# LVDS.net
KiCad netlist of a schematic drawn in Altium Designer
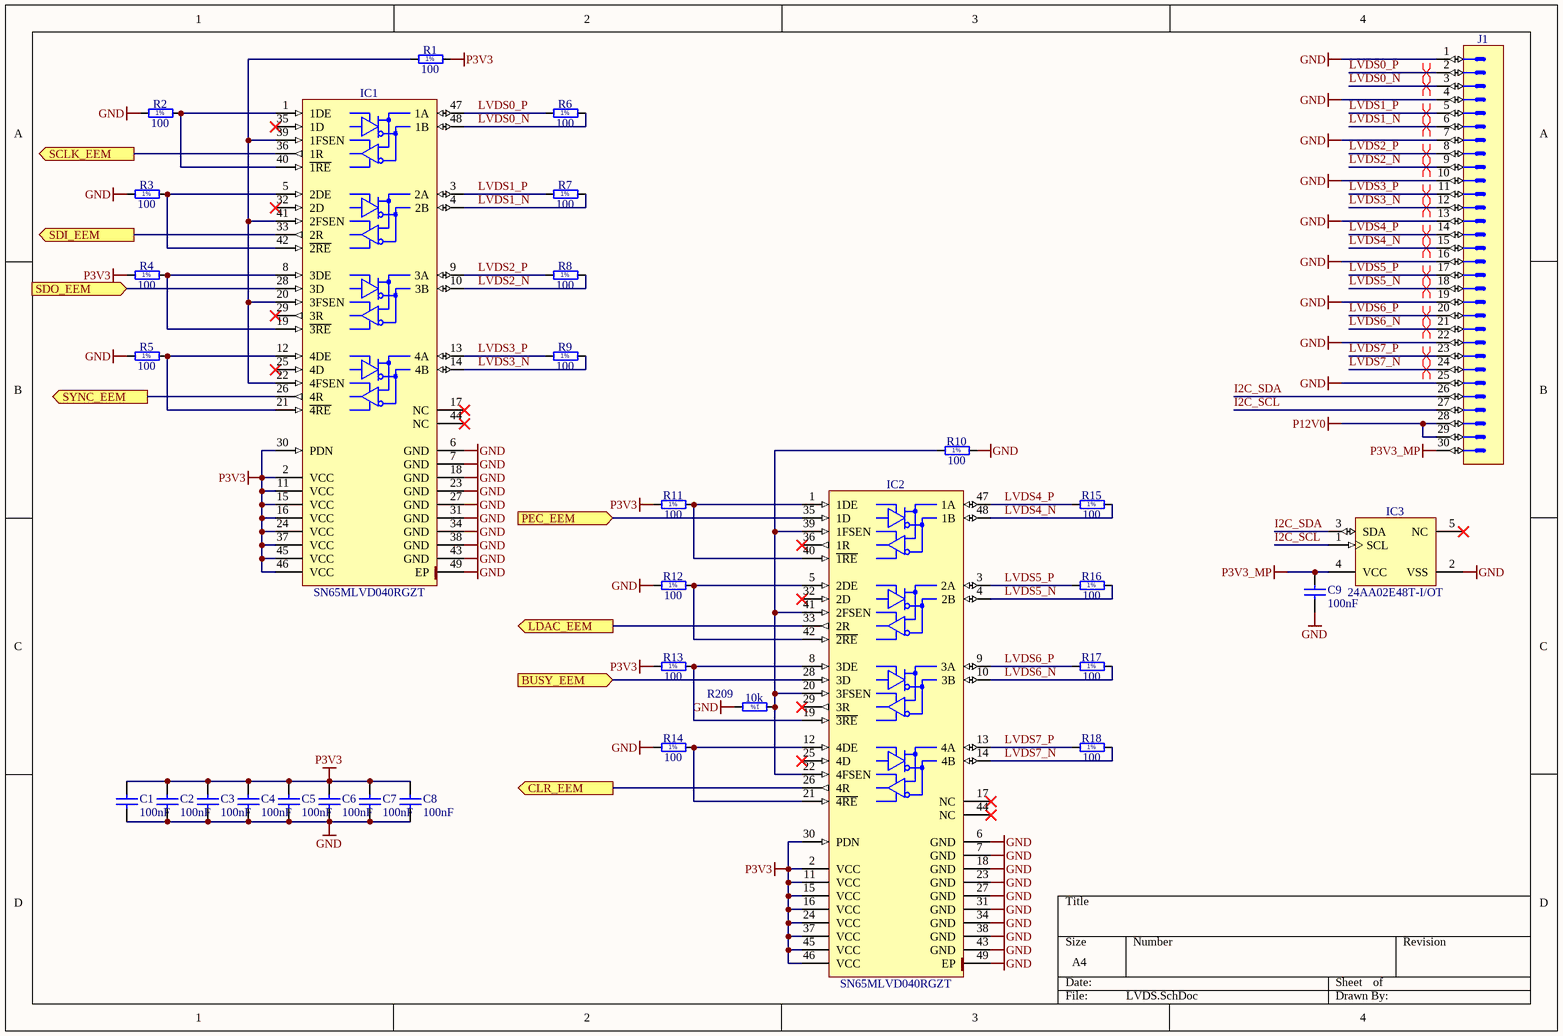
[diagram p0: LVDS.SchDoc]

(export (version "E")
  (design (tool "Eeschema 10.0.6"))
  (components
    (comp (ref "C1")
      (value "100nF")
      (footprint "C0402C104K4RACTU")
      (description "Capacitor; Ceramic; Cap; .100uF; Tol 10%; SMT; Vol-Rtg 16V; X7R; Tape and Reel")
      (fields (field (name "TOLERANCE") "10%"))
      (libsource (lib "CapacitorLibrary") (part "C0402C104K4RACTU"))
    )
    (comp (ref "C2")
      (value "100nF")
      (footprint "C0402C104K4RACTU")
      (description "Capacitor; Ceramic; Cap; .100uF; Tol 10%; SMT; Vol-Rtg 16V; X7R; Tape and Reel")
      (fields (field (name "TOLERANCE") "10%"))
      (libsource (lib "CapacitorLibrary") (part "C0402C104K4RACTU"))
    )
    (comp (ref "C3")
      (value "100nF")
      (footprint "C0402C104K4RACTU")
      (description "Capacitor; Ceramic; Cap; .100uF; Tol 10%; SMT; Vol-Rtg 16V; X7R; Tape and Reel")
      (fields (field (name "TOLERANCE") "10%"))
      (libsource (lib "CapacitorLibrary") (part "C0402C104K4RACTU"))
    )
    (comp (ref "C4")
      (value "100nF")
      (footprint "C0402C104K4RACTU")
      (description "Capacitor; Ceramic; Cap; .100uF; Tol 10%; SMT; Vol-Rtg 16V; X7R; Tape and Reel")
      (fields (field (name "TOLERANCE") "10%"))
      (libsource (lib "CapacitorLibrary") (part "C0402C104K4RACTU"))
    )
    (comp (ref "C5")
      (value "100nF")
      (footprint "C0402C104K4RACTU")
      (description "Capacitor; Ceramic; Cap; .100uF; Tol 10%; SMT; Vol-Rtg 16V; X7R; Tape and Reel")
      (fields (field (name "TOLERANCE") "10%"))
      (libsource (lib "CapacitorLibrary") (part "C0402C104K4RACTU"))
    )
    (comp (ref "C6")
      (value "100nF")
      (footprint "C0402C104K4RACTU")
      (description "Capacitor; Ceramic; Cap; .100uF; Tol 10%; SMT; Vol-Rtg 16V; X7R; Tape and Reel")
      (fields (field (name "TOLERANCE") "10%"))
      (libsource (lib "CapacitorLibrary") (part "C0402C104K4RACTU"))
    )
    (comp (ref "C7")
      (value "100nF")
      (footprint "C0402C104K4RACTU")
      (description "Capacitor; Ceramic; Cap; .100uF; Tol 10%; SMT; Vol-Rtg 16V; X7R; Tape and Reel")
      (fields (field (name "TOLERANCE") "10%"))
      (libsource (lib "CapacitorLibrary") (part "C0402C104K4RACTU"))
    )
    (comp (ref "C8")
      (value "100nF")
      (footprint "C0402C104K4RACTU")
      (description "Capacitor; Ceramic; Cap; .100uF; Tol 10%; SMT; Vol-Rtg 16V; X7R; Tape and Reel")
      (fields (field (name "TOLERANCE") "10%"))
      (libsource (lib "CapacitorLibrary") (part "C0402C104K4RACTU"))
    )
    (comp (ref "C9")
      (value "100nF")
      (footprint "C0402C104K4RACTU")
      (description "Capacitor; Ceramic; Cap; .100uF; Tol 10%; SMT; Vol-Rtg 16V; X7R; Tape and Reel")
      (fields (field (name "TOLERANCE") "10%"))
      (libsource (lib "CapacitorLibrary") (part "C0402C104K4RACTU"))
    )
    (comp (ref "IC1")
      (value "SN65MLVD040RGZT")
      (footprint "QFN50P700X700X100-49N-S420")
      (description "4-Channel Half-Duplex M-LVDS Line Transceiver")
      (fields (field (name "MANUFACTURER") "TEXAS INSTRUMENTS") (field (name "AUTHOR") "CERN DEM JLC"))
      (libsource (lib "ICs And Semiconductors") (part "SN65MLVD040"))
    )
    (comp (ref "IC2")
      (value "SN65MLVD040RGZT")
      (footprint "QFN50P700X700X100-49N-S420")
      (description "4-Channel Half-Duplex M-LVDS Line Transceiver")
      (fields (field (name "MANUFACTURER") "TEXAS INSTRUMENTS") (field (name "AUTHOR") "CERN DEM JLC"))
      (libsource (lib "ICs And Semiconductors") (part "SN65MLVD040"))
    )
    (comp (ref "IC3")
      (value "24AA02E48T-I/OT")
      (footprint "SOT95P280X145-5N")
      (description "1.7V-5.5V, 2K I2C Serial EEPROM With EUI-48 Node Identity")
      (fields (field (name "MANUFACTURER") "MICROCHIP TECHNOLOGY") (field (name "AUTHOR") "CERN DEM MR"))
      (libsource (lib "ICs And Semiconductors") (part "24AA02E48T-I/OT"))
    )
    (comp (ref "J1")
      (value "Header 30")
      (footprint "3M_N2530-6002RB")
      (description "Connector 30 Male")
      (fields
        (field (name "PART NUMBER") "3M_N2530-6002RB")
        (field (name "MANUFACTURER") "3M")
        (field (name "AUTHOR") "CERN DEM JLC")
      )
      (libsource (lib "Connectors") (part "Connector 30 Male"))
    )
    (comp (ref "R1")
      (value "100")
      (footprint "RESC1005X40N")
      (description "Resistor - 1%")
      (fields
        (field (name "PART NUMBER") "R0402_100R_1%_0.1W_100PPM")
        (field (name "POWER") "0.1W")
        (field (name "AUTHOR") "CERN DEM JLC")
      )
      (libsource (lib "Resistors") (part "Resistor - 1%"))
    )
    (comp (ref "R2")
      (value "100")
      (footprint "RESC1005X40N")
      (description "Resistor - 1%")
      (fields
        (field (name "PART NUMBER") "R0402_100R_1%_0.1W_100PPM")
        (field (name "POWER") "0.1W")
        (field (name "AUTHOR") "CERN DEM JLC")
      )
      (libsource (lib "Resistors") (part "Resistor - 1%"))
    )
    (comp (ref "R3")
      (value "100")
      (footprint "RESC1005X40N")
      (description "Resistor - 1%")
      (fields
        (field (name "PART NUMBER") "R0402_100R_1%_0.1W_100PPM")
        (field (name "POWER") "0.1W")
        (field (name "AUTHOR") "CERN DEM JLC")
      )
      (libsource (lib "Resistors") (part "Resistor - 1%"))
    )
    (comp (ref "R4")
      (value "100")
      (footprint "RESC1005X40N")
      (description "Resistor - 1%")
      (fields
        (field (name "PART NUMBER") "R0402_100R_1%_0.1W_100PPM")
        (field (name "POWER") "0.1W")
        (field (name "AUTHOR") "CERN DEM JLC")
      )
      (libsource (lib "Resistors") (part "Resistor - 1%"))
    )
    (comp (ref "R5")
      (value "100")
      (footprint "RESC1005X40N")
      (description "Resistor - 1%")
      (fields
        (field (name "PART NUMBER") "R0402_100R_1%_0.1W_100PPM")
        (field (name "POWER") "0.1W")
        (field (name "AUTHOR") "CERN DEM JLC")
      )
      (libsource (lib "Resistors") (part "Resistor - 1%"))
    )
    (comp (ref "R6")
      (value "100")
      (footprint "RESC1005X40N")
      (description "Resistor - 1%")
      (fields
        (field (name "PART NUMBER") "R0402_100R_1%_0.1W_100PPM")
        (field (name "POWER") "0.1W")
        (field (name "AUTHOR") "CERN DEM JLC")
      )
      (libsource (lib "Resistors") (part "Resistor - 1%"))
    )
    (comp (ref "R7")
      (value "100")
      (footprint "RESC1005X40N")
      (description "Resistor - 1%")
      (fields
        (field (name "PART NUMBER") "R0402_100R_1%_0.1W_100PPM")
        (field (name "POWER") "0.1W")
        (field (name "AUTHOR") "CERN DEM JLC")
      )
      (libsource (lib "Resistors") (part "Resistor - 1%"))
    )
    (comp (ref "R8")
      (value "100")
      (footprint "RESC1005X40N")
      (description "Resistor - 1%")
      (fields
        (field (name "PART NUMBER") "R0402_100R_1%_0.1W_100PPM")
        (field (name "POWER") "0.1W")
        (field (name "AUTHOR") "CERN DEM JLC")
      )
      (libsource (lib "Resistors") (part "Resistor - 1%"))
    )
    (comp (ref "R9")
      (value "100")
      (footprint "RESC1005X40N")
      (description "Resistor - 1%")
      (fields
        (field (name "PART NUMBER") "R0402_100R_1%_0.1W_100PPM")
        (field (name "POWER") "0.1W")
        (field (name "AUTHOR") "CERN DEM JLC")
      )
      (libsource (lib "Resistors") (part "Resistor - 1%"))
    )
    (comp (ref "R10")
      (value "100")
      (footprint "RESC1005X40N")
      (description "Resistor - 1%")
      (fields
        (field (name "PART NUMBER") "R0402_100R_1%_0.1W_100PPM")
        (field (name "POWER") "0.1W")
        (field (name "AUTHOR") "CERN DEM JLC")
      )
      (libsource (lib "Resistors") (part "Resistor - 1%"))
    )
    (comp (ref "R11")
      (value "100")
      (footprint "RESC1005X40N")
      (description "Resistor - 1%")
      (fields
        (field (name "PART NUMBER") "R0402_100R_1%_0.1W_100PPM")
        (field (name "POWER") "0.1W")
        (field (name "AUTHOR") "CERN DEM JLC")
      )
      (libsource (lib "Resistors") (part "Resistor - 1%"))
    )
    (comp (ref "R12")
      (value "100")
      (footprint "RESC1005X40N")
      (description "Resistor - 1%")
      (fields
        (field (name "PART NUMBER") "R0402_100R_1%_0.1W_100PPM")
        (field (name "POWER") "0.1W")
        (field (name "AUTHOR") "CERN DEM JLC")
      )
      (libsource (lib "Resistors") (part "Resistor - 1%"))
    )
    (comp (ref "R13")
      (value "100")
      (footprint "RESC1005X40N")
      (description "Resistor - 1%")
      (fields
        (field (name "PART NUMBER") "R0402_100R_1%_0.1W_100PPM")
        (field (name "POWER") "0.1W")
        (field (name "AUTHOR") "CERN DEM JLC")
      )
      (libsource (lib "Resistors") (part "Resistor - 1%"))
    )
    (comp (ref "R14")
      (value "100")
      (footprint "RESC1005X40N")
      (description "Resistor - 1%")
      (fields
        (field (name "PART NUMBER") "R0402_100R_1%_0.1W_100PPM")
        (field (name "POWER") "0.1W")
        (field (name "AUTHOR") "CERN DEM JLC")
      )
      (libsource (lib "Resistors") (part "Resistor - 1%"))
    )
    (comp (ref "R15")
      (value "100")
      (footprint "RESC1005X40N")
      (description "Resistor - 1%")
      (fields
        (field (name "PART NUMBER") "R0402_100R_1%_0.1W_100PPM")
        (field (name "POWER") "0.1W")
        (field (name "AUTHOR") "CERN DEM JLC")
      )
      (libsource (lib "Resistors") (part "Resistor - 1%"))
    )
    (comp (ref "R16")
      (value "100")
      (footprint "RESC1005X40N")
      (description "Resistor - 1%")
      (fields
        (field (name "PART NUMBER") "R0402_100R_1%_0.1W_100PPM")
        (field (name "POWER") "0.1W")
        (field (name "AUTHOR") "CERN DEM JLC")
      )
      (libsource (lib "Resistors") (part "Resistor - 1%"))
    )
    (comp (ref "R17")
      (value "100")
      (footprint "RESC1005X40N")
      (description "Resistor - 1%")
      (fields
        (field (name "PART NUMBER") "R0402_100R_1%_0.1W_100PPM")
        (field (name "POWER") "0.1W")
        (field (name "AUTHOR") "CERN DEM JLC")
      )
      (libsource (lib "Resistors") (part "Resistor - 1%"))
    )
    (comp (ref "R18")
      (value "100")
      (footprint "RESC1005X40N")
      (description "Resistor - 1%")
      (fields
        (field (name "PART NUMBER") "R0402_100R_1%_0.1W_100PPM")
        (field (name "POWER") "0.1W")
        (field (name "AUTHOR") "CERN DEM JLC")
      )
      (libsource (lib "Resistors") (part "Resistor - 1%"))
    )
    (comp (ref "R209")
      (value "10k")
      (footprint "RESC1005X40N")
      (description "Resistor - 1%")
      (fields
        (field (name "PART NUMBER") "R0402_10K_1%_0.0625W_100PPM")
        (field (name "POWER") "0.0625W")
        (field (name "AUTHOR") "CERN DEM JLC")
      )
      (libsource (lib "Resistors") (part "Resistor - 1%"))
    )
  )
  (nets
    (net (code "1") (name "/BUSY_EEM") (class "Default")
      (node (ref "IC2") (pin "28") (pinfunction "3D_28") (pintype "input"))
    )
    (net (code "2") (name "/CLR_EEM") (class "Default")
      (node (ref "IC2") (pin "26") (pinfunction "4R_26") (pintype "output"))
    )
    (net (code "3") (name "/I2C_SCL") (class "Default")
      (node (ref "IC3") (pin "1") (pinfunction "SCL_1") (pintype "input"))
      (node (ref "J1") (pin "27") (pinfunction "27_27") (pintype "bidirectional"))
    )
    (net (code "4") (name "/I2C_SDA") (class "Default")
      (node (ref "IC3") (pin "3") (pinfunction "SDA_3") (pintype "bidirectional"))
      (node (ref "J1") (pin "26") (pinfunction "26_26") (pintype "bidirectional"))
    )
    (net (code "5") (name "/LDAC_EEM") (class "Default")
      (node (ref "IC2") (pin "33") (pinfunction "2R_33") (pintype "output"))
    )
    (net (code "6") (name "/LVDS0_N") (class "Default")
      (node (ref "IC1") (pin "48") (pinfunction "1B_48") (pintype "bidirectional"))
      (node (ref "J1") (pin "3") (pinfunction "3_3") (pintype "bidirectional"))
      (node (ref "R6") (pin "2") (pinfunction "2_2") (pintype "passive"))
    )
    (net (code "7") (name "/LVDS0_P") (class "Default")
      (node (ref "IC1") (pin "47") (pinfunction "1A_47") (pintype "bidirectional"))
      (node (ref "J1") (pin "2") (pinfunction "2_2") (pintype "bidirectional"))
      (node (ref "R6") (pin "1") (pinfunction "1_1") (pintype "passive"))
    )
    (net (code "8") (name "/LVDS1_N") (class "Default")
      (node (ref "IC1") (pin "4") (pinfunction "2B_4") (pintype "bidirectional"))
      (node (ref "J1") (pin "6") (pinfunction "6_6") (pintype "bidirectional"))
      (node (ref "R7") (pin "2") (pinfunction "2_2") (pintype "passive"))
    )
    (net (code "9") (name "/LVDS1_P") (class "Default")
      (node (ref "IC1") (pin "3") (pinfunction "2A_3") (pintype "bidirectional"))
      (node (ref "J1") (pin "5") (pinfunction "5_5") (pintype "bidirectional"))
      (node (ref "R7") (pin "1") (pinfunction "1_1") (pintype "passive"))
    )
    (net (code "10") (name "/LVDS2_N") (class "Default")
      (node (ref "IC1") (pin "10") (pinfunction "3B_10") (pintype "bidirectional"))
      (node (ref "J1") (pin "9") (pinfunction "9_9") (pintype "bidirectional"))
      (node (ref "R8") (pin "2") (pinfunction "2_2") (pintype "passive"))
    )
    (net (code "11") (name "/LVDS2_P") (class "Default")
      (node (ref "IC1") (pin "9") (pinfunction "3A_9") (pintype "bidirectional"))
      (node (ref "J1") (pin "8") (pinfunction "8_8") (pintype "bidirectional"))
      (node (ref "R8") (pin "1") (pinfunction "1_1") (pintype "passive"))
    )
    (net (code "12") (name "/LVDS3_N") (class "Default")
      (node (ref "IC1") (pin "14") (pinfunction "4B_14") (pintype "bidirectional"))
      (node (ref "J1") (pin "12") (pinfunction "12_12") (pintype "bidirectional"))
      (node (ref "R9") (pin "2") (pinfunction "2_2") (pintype "passive"))
    )
    (net (code "13") (name "/LVDS3_P") (class "Default")
      (node (ref "IC1") (pin "13") (pinfunction "4A_13") (pintype "bidirectional"))
      (node (ref "J1") (pin "11") (pinfunction "11_11") (pintype "bidirectional"))
      (node (ref "R9") (pin "1") (pinfunction "1_1") (pintype "passive"))
    )
    (net (code "14") (name "/LVDS4_N") (class "Default")
      (node (ref "IC2") (pin "48") (pinfunction "1B_48") (pintype "bidirectional"))
      (node (ref "J1") (pin "15") (pinfunction "15_15") (pintype "bidirectional"))
      (node (ref "R15") (pin "2") (pinfunction "2_2") (pintype "passive"))
    )
    (net (code "15") (name "/LVDS4_P") (class "Default")
      (node (ref "IC2") (pin "47") (pinfunction "1A_47") (pintype "bidirectional"))
      (node (ref "J1") (pin "14") (pinfunction "14_14") (pintype "bidirectional"))
      (node (ref "R15") (pin "1") (pinfunction "1_1") (pintype "passive"))
    )
    (net (code "16") (name "/LVDS5_N") (class "Default")
      (node (ref "IC2") (pin "4") (pinfunction "2B_4") (pintype "bidirectional"))
      (node (ref "J1") (pin "18") (pinfunction "18_18") (pintype "bidirectional"))
      (node (ref "R16") (pin "2") (pinfunction "2_2") (pintype "passive"))
    )
    (net (code "17") (name "/LVDS5_P") (class "Default")
      (node (ref "IC2") (pin "3") (pinfunction "2A_3") (pintype "bidirectional"))
      (node (ref "J1") (pin "17") (pinfunction "17_17") (pintype "bidirectional"))
      (node (ref "R16") (pin "1") (pinfunction "1_1") (pintype "passive"))
    )
    (net (code "18") (name "/LVDS6_N") (class "Default")
      (node (ref "IC2") (pin "10") (pinfunction "3B_10") (pintype "bidirectional"))
      (node (ref "J1") (pin "21") (pinfunction "21_21") (pintype "bidirectional"))
      (node (ref "R17") (pin "2") (pinfunction "2_2") (pintype "passive"))
    )
    (net (code "19") (name "/LVDS6_P") (class "Default")
      (node (ref "IC2") (pin "9") (pinfunction "3A_9") (pintype "bidirectional"))
      (node (ref "J1") (pin "20") (pinfunction "20_20") (pintype "bidirectional"))
      (node (ref "R17") (pin "1") (pinfunction "1_1") (pintype "passive"))
    )
    (net (code "20") (name "/LVDS7_N") (class "Default")
      (node (ref "IC2") (pin "14") (pinfunction "4B_14") (pintype "bidirectional"))
      (node (ref "J1") (pin "24") (pinfunction "24_24") (pintype "bidirectional"))
      (node (ref "R18") (pin "2") (pinfunction "2_2") (pintype "passive"))
    )
    (net (code "21") (name "/LVDS7_P") (class "Default")
      (node (ref "IC2") (pin "13") (pinfunction "4A_13") (pintype "bidirectional"))
      (node (ref "J1") (pin "23") (pinfunction "23_23") (pintype "bidirectional"))
      (node (ref "R18") (pin "1") (pinfunction "1_1") (pintype "passive"))
    )
    (net (code "22") (name "/PEC_EEM") (class "Default")
      (node (ref "IC2") (pin "35") (pinfunction "1D_35") (pintype "input"))
    )
    (net (code "23") (name "/SCLK_EEM") (class "Default")
      (node (ref "IC1") (pin "36") (pinfunction "1R_36") (pintype "output"))
    )
    (net (code "24") (name "/SDI_EEM") (class "Default")
      (node (ref "IC1") (pin "33") (pinfunction "2R_33") (pintype "output"))
    )
    (net (code "25") (name "/SDO_EEM") (class "Default")
      (node (ref "IC1") (pin "28") (pinfunction "3D_28") (pintype "input"))
    )
    (net (code "26") (name "/SYNC_EEM") (class "Default")
      (node (ref "IC1") (pin "26") (pinfunction "4R_26") (pintype "output"))
    )
    (net (code "27") (name "GND") (class "Default")
      (node (ref "C1") (pin "1") (pinfunction "1_1") (pintype "passive"))
      (node (ref "C2") (pin "1") (pinfunction "1_1") (pintype "passive"))
      (node (ref "C3") (pin "1") (pinfunction "1_1") (pintype "passive"))
      (node (ref "C4") (pin "1") (pinfunction "1_1") (pintype "passive"))
      (node (ref "C5") (pin "1") (pinfunction "1_1") (pintype "passive"))
      (node (ref "C6") (pin "1") (pinfunction "1_1") (pintype "passive"))
      (node (ref "C7") (pin "1") (pinfunction "1_1") (pintype "passive"))
      (node (ref "C8") (pin "1") (pinfunction "1_1") (pintype "passive"))
      (node (ref "C9") (pin "1") (pinfunction "1_1") (pintype "passive"))
      (node (ref "IC1") (pin "18") (pinfunction "GND_18") (pintype "power_in"))
      (node (ref "IC1") (pin "23") (pinfunction "GND_23") (pintype "power_in"))
      (node (ref "IC1") (pin "27") (pinfunction "GND_27") (pintype "power_in"))
      (node (ref "IC1") (pin "31") (pinfunction "GND_31") (pintype "power_in"))
      (node (ref "IC1") (pin "34") (pinfunction "GND_34") (pintype "power_in"))
      (node (ref "IC1") (pin "38") (pinfunction "GND_38") (pintype "power_in"))
      (node (ref "IC1") (pin "43") (pinfunction "GND_43") (pintype "power_in"))
      (node (ref "IC1") (pin "49") (pinfunction "EP_49") (pintype "power_in"))
      (node (ref "IC1") (pin "6") (pinfunction "GND_6") (pintype "power_in"))
      (node (ref "IC1") (pin "7") (pinfunction "GND_7") (pintype "power_in"))
      (node (ref "IC2") (pin "18") (pinfunction "GND_18") (pintype "power_in"))
      (node (ref "IC2") (pin "23") (pinfunction "GND_23") (pintype "power_in"))
      (node (ref "IC2") (pin "27") (pinfunction "GND_27") (pintype "power_in"))
      (node (ref "IC2") (pin "31") (pinfunction "GND_31") (pintype "power_in"))
      (node (ref "IC2") (pin "34") (pinfunction "GND_34") (pintype "power_in"))
      (node (ref "IC2") (pin "38") (pinfunction "GND_38") (pintype "power_in"))
      (node (ref "IC2") (pin "43") (pinfunction "GND_43") (pintype "power_in"))
      (node (ref "IC2") (pin "49") (pinfunction "EP_49") (pintype "power_in"))
      (node (ref "IC2") (pin "6") (pinfunction "GND_6") (pintype "power_in"))
      (node (ref "IC2") (pin "7") (pinfunction "GND_7") (pintype "power_in"))
      (node (ref "IC3") (pin "2") (pinfunction "VSS_2") (pintype "power_in"))
      (node (ref "J1") (pin "1") (pinfunction "1_1") (pintype "bidirectional"))
      (node (ref "J1") (pin "10") (pinfunction "10_10") (pintype "bidirectional"))
      (node (ref "J1") (pin "13") (pinfunction "13_13") (pintype "bidirectional"))
      (node (ref "J1") (pin "16") (pinfunction "16_16") (pintype "bidirectional"))
      (node (ref "J1") (pin "19") (pinfunction "19_19") (pintype "bidirectional"))
      (node (ref "J1") (pin "22") (pinfunction "22_22") (pintype "bidirectional"))
      (node (ref "J1") (pin "25") (pinfunction "25_25") (pintype "bidirectional"))
      (node (ref "J1") (pin "4") (pinfunction "4_4") (pintype "bidirectional"))
      (node (ref "J1") (pin "7") (pinfunction "7_7") (pintype "bidirectional"))
      (node (ref "R10") (pin "2") (pinfunction "2_2") (pintype "passive"))
      (node (ref "R12") (pin "1") (pinfunction "1_1") (pintype "passive"))
      (node (ref "R14") (pin "1") (pinfunction "1_1") (pintype "passive"))
      (node (ref "R2") (pin "1") (pinfunction "1_1") (pintype "passive"))
      (node (ref "R209") (pin "2") (pinfunction "2_2") (pintype "passive"))
      (node (ref "R3") (pin "1") (pinfunction "1_1") (pintype "passive"))
      (node (ref "R5") (pin "1") (pinfunction "1_1") (pintype "passive"))
    )
    (net (code "28") (name "Net-(IC1-1DE)") (class "Default")
      (node (ref "IC1") (pin "1") (pinfunction "1DE_1") (pintype "input"))
      (node (ref "IC1") (pin "40") (pinfunction "~{1RE}_40") (pintype "input"))
      (node (ref "R2") (pin "2") (pinfunction "2_2") (pintype "passive"))
    )
    (net (code "29") (name "Net-(IC1-1FSEN)") (class "Default")
      (node (ref "IC1") (pin "20") (pinfunction "3FSEN_20") (pintype "input"))
      (node (ref "IC1") (pin "22") (pinfunction "4FSEN_22") (pintype "input"))
      (node (ref "IC1") (pin "39") (pinfunction "1FSEN_39") (pintype "input"))
      (node (ref "IC1") (pin "41") (pinfunction "2FSEN_41") (pintype "input"))
      (node (ref "R1") (pin "1") (pinfunction "1_1") (pintype "passive"))
    )
    (net (code "30") (name "Net-(IC1-2DE)") (class "Default")
      (node (ref "IC1") (pin "42") (pinfunction "~{2RE}_42") (pintype "input"))
      (node (ref "IC1") (pin "5") (pinfunction "2DE_5") (pintype "input"))
      (node (ref "R3") (pin "2") (pinfunction "2_2") (pintype "passive"))
    )
    (net (code "31") (name "Net-(IC1-3DE)") (class "Default")
      (node (ref "IC1") (pin "19") (pinfunction "~{3RE}_19") (pintype "input"))
      (node (ref "IC1") (pin "8") (pinfunction "3DE_8") (pintype "input"))
      (node (ref "R4") (pin "2") (pinfunction "2_2") (pintype "passive"))
    )
    (net (code "32") (name "Net-(IC1-4DE)") (class "Default")
      (node (ref "IC1") (pin "12") (pinfunction "4DE_12") (pintype "input"))
      (node (ref "IC1") (pin "21") (pinfunction "~{4RE}_21") (pintype "input"))
      (node (ref "R5") (pin "2") (pinfunction "2_2") (pintype "passive"))
    )
    (net (code "33") (name "Net-(IC2-1DE)") (class "Default")
      (node (ref "IC2") (pin "1") (pinfunction "1DE_1") (pintype "input"))
      (node (ref "IC2") (pin "40") (pinfunction "~{1RE}_40") (pintype "input"))
      (node (ref "R11") (pin "2") (pinfunction "2_2") (pintype "passive"))
    )
    (net (code "34") (name "Net-(IC2-1FSEN)") (class "Default")
      (node (ref "IC2") (pin "20") (pinfunction "3FSEN_20") (pintype "input"))
      (node (ref "IC2") (pin "22") (pinfunction "4FSEN_22") (pintype "input"))
      (node (ref "IC2") (pin "39") (pinfunction "1FSEN_39") (pintype "input"))
      (node (ref "IC2") (pin "41") (pinfunction "2FSEN_41") (pintype "input"))
      (node (ref "R10") (pin "1") (pinfunction "1_1") (pintype "passive"))
      (node (ref "R209") (pin "1") (pinfunction "1_1") (pintype "passive"))
    )
    (net (code "35") (name "Net-(IC2-2DE)") (class "Default")
      (node (ref "IC2") (pin "42") (pinfunction "~{2RE}_42") (pintype "input"))
      (node (ref "IC2") (pin "5") (pinfunction "2DE_5") (pintype "input"))
      (node (ref "R12") (pin "2") (pinfunction "2_2") (pintype "passive"))
    )
    (net (code "36") (name "Net-(IC2-3DE)") (class "Default")
      (node (ref "IC2") (pin "19") (pinfunction "~{3RE}_19") (pintype "input"))
      (node (ref "IC2") (pin "8") (pinfunction "3DE_8") (pintype "input"))
      (node (ref "R13") (pin "2") (pinfunction "2_2") (pintype "passive"))
    )
    (net (code "37") (name "Net-(IC2-4DE)") (class "Default")
      (node (ref "IC2") (pin "12") (pinfunction "4DE_12") (pintype "input"))
      (node (ref "IC2") (pin "21") (pinfunction "~{4RE}_21") (pintype "input"))
      (node (ref "R14") (pin "2") (pinfunction "2_2") (pintype "passive"))
    )
    (net (code "38") (name "P3V3") (class "Default")
      (node (ref "C1") (pin "2") (pinfunction "2_2") (pintype "passive"))
      (node (ref "C2") (pin "2") (pinfunction "2_2") (pintype "passive"))
      (node (ref "C3") (pin "2") (pinfunction "2_2") (pintype "passive"))
      (node (ref "C4") (pin "2") (pinfunction "2_2") (pintype "passive"))
      (node (ref "C5") (pin "2") (pinfunction "2_2") (pintype "passive"))
      (node (ref "C6") (pin "2") (pinfunction "2_2") (pintype "passive"))
      (node (ref "C7") (pin "2") (pinfunction "2_2") (pintype "passive"))
      (node (ref "C8") (pin "2") (pinfunction "2_2") (pintype "passive"))
      (node (ref "IC1") (pin "11") (pinfunction "VCC_11") (pintype "power_in"))
      (node (ref "IC1") (pin "15") (pinfunction "VCC_15") (pintype "power_in"))
      (node (ref "IC1") (pin "16") (pinfunction "VCC_16") (pintype "power_in"))
      (node (ref "IC1") (pin "2") (pinfunction "VCC_2") (pintype "power_in"))
      (node (ref "IC1") (pin "24") (pinfunction "VCC_24") (pintype "power_in"))
      (node (ref "IC1") (pin "30") (pinfunction "PDN_30") (pintype "input"))
      (node (ref "IC1") (pin "37") (pinfunction "VCC_37") (pintype "power_in"))
      (node (ref "IC1") (pin "45") (pinfunction "VCC_45") (pintype "power_in"))
      (node (ref "IC1") (pin "46") (pinfunction "VCC_46") (pintype "power_in"))
      (node (ref "IC2") (pin "11") (pinfunction "VCC_11") (pintype "power_in"))
      (node (ref "IC2") (pin "15") (pinfunction "VCC_15") (pintype "power_in"))
      (node (ref "IC2") (pin "16") (pinfunction "VCC_16") (pintype "power_in"))
      (node (ref "IC2") (pin "2") (pinfunction "VCC_2") (pintype "power_in"))
      (node (ref "IC2") (pin "24") (pinfunction "VCC_24") (pintype "power_in"))
      (node (ref "IC2") (pin "30") (pinfunction "PDN_30") (pintype "input"))
      (node (ref "IC2") (pin "37") (pinfunction "VCC_37") (pintype "power_in"))
      (node (ref "IC2") (pin "45") (pinfunction "VCC_45") (pintype "power_in"))
      (node (ref "IC2") (pin "46") (pinfunction "VCC_46") (pintype "power_in"))
      (node (ref "R1") (pin "2") (pinfunction "2_2") (pintype "passive"))
      (node (ref "R11") (pin "1") (pinfunction "1_1") (pintype "passive"))
      (node (ref "R13") (pin "1") (pinfunction "1_1") (pintype "passive"))
      (node (ref "R4") (pin "1") (pinfunction "1_1") (pintype "passive"))
    )
    (net (code "39") (name "P3V3_MP") (class "Default")
      (node (ref "C9") (pin "2") (pinfunction "2_2") (pintype "passive"))
      (node (ref "IC3") (pin "4") (pinfunction "VCC_4") (pintype "power_in"))
      (node (ref "J1") (pin "30") (pinfunction "30_30") (pintype "bidirectional"))
    )
    (net (code "40") (name "P12V0") (class "Default")
      (node (ref "J1") (pin "28") (pinfunction "28_28") (pintype "bidirectional"))
      (node (ref "J1") (pin "29") (pinfunction "29_29") (pintype "bidirectional"))
    )
    (net (code "41") (name "unconnected-(IC1-1D-Pad35)") (class "Default")
      (node (ref "IC1") (pin "35") (pinfunction "1D_35") (pintype "input+no_connect"))
    )
    (net (code "42") (name "unconnected-(IC1-2D-Pad32)") (class "Default")
      (node (ref "IC1") (pin "32") (pinfunction "2D_32") (pintype "input+no_connect"))
    )
    (net (code "43") (name "unconnected-(IC1-3R-Pad29)") (class "Default")
      (node (ref "IC1") (pin "29") (pinfunction "3R_29") (pintype "output+no_connect"))
    )
    (net (code "44") (name "unconnected-(IC1-4D-Pad25)") (class "Default")
      (node (ref "IC1") (pin "25") (pinfunction "4D_25") (pintype "input+no_connect"))
    )
    (net (code "45") (name "unconnected-(IC1-NC-Pad17)") (class "Default")
      (node (ref "IC1") (pin "17") (pinfunction "NC_17") (pintype "passive+no_connect"))
    )
    (net (code "46") (name "unconnected-(IC1-NC-Pad44)") (class "Default")
      (node (ref "IC1") (pin "44") (pinfunction "NC_44") (pintype "passive+no_connect"))
    )
    (net (code "47") (name "unconnected-(IC2-1R-Pad36)") (class "Default")
      (node (ref "IC2") (pin "36") (pinfunction "1R_36") (pintype "output+no_connect"))
    )
    (net (code "48") (name "unconnected-(IC2-2D-Pad32)") (class "Default")
      (node (ref "IC2") (pin "32") (pinfunction "2D_32") (pintype "input+no_connect"))
    )
    (net (code "49") (name "unconnected-(IC2-3R-Pad29)") (class "Default")
      (node (ref "IC2") (pin "29") (pinfunction "3R_29") (pintype "output+no_connect"))
    )
    (net (code "50") (name "unconnected-(IC2-4D-Pad25)") (class "Default")
      (node (ref "IC2") (pin "25") (pinfunction "4D_25") (pintype "input+no_connect"))
    )
    (net (code "51") (name "unconnected-(IC2-NC-Pad17)") (class "Default")
      (node (ref "IC2") (pin "17") (pinfunction "NC_17") (pintype "passive+no_connect"))
    )
    (net (code "52") (name "unconnected-(IC2-NC-Pad44)") (class "Default")
      (node (ref "IC2") (pin "44") (pinfunction "NC_44") (pintype "passive+no_connect"))
    )
    (net (code "53") (name "unconnected-(IC3-NC-Pad5)") (class "Default")
      (node (ref "IC3") (pin "5") (pinfunction "NC_5") (pintype "passive+no_connect"))
    )
  )
)
